# 04-USB-TFT.net
KiCad netlist of a schematic drawn in Altium Designer
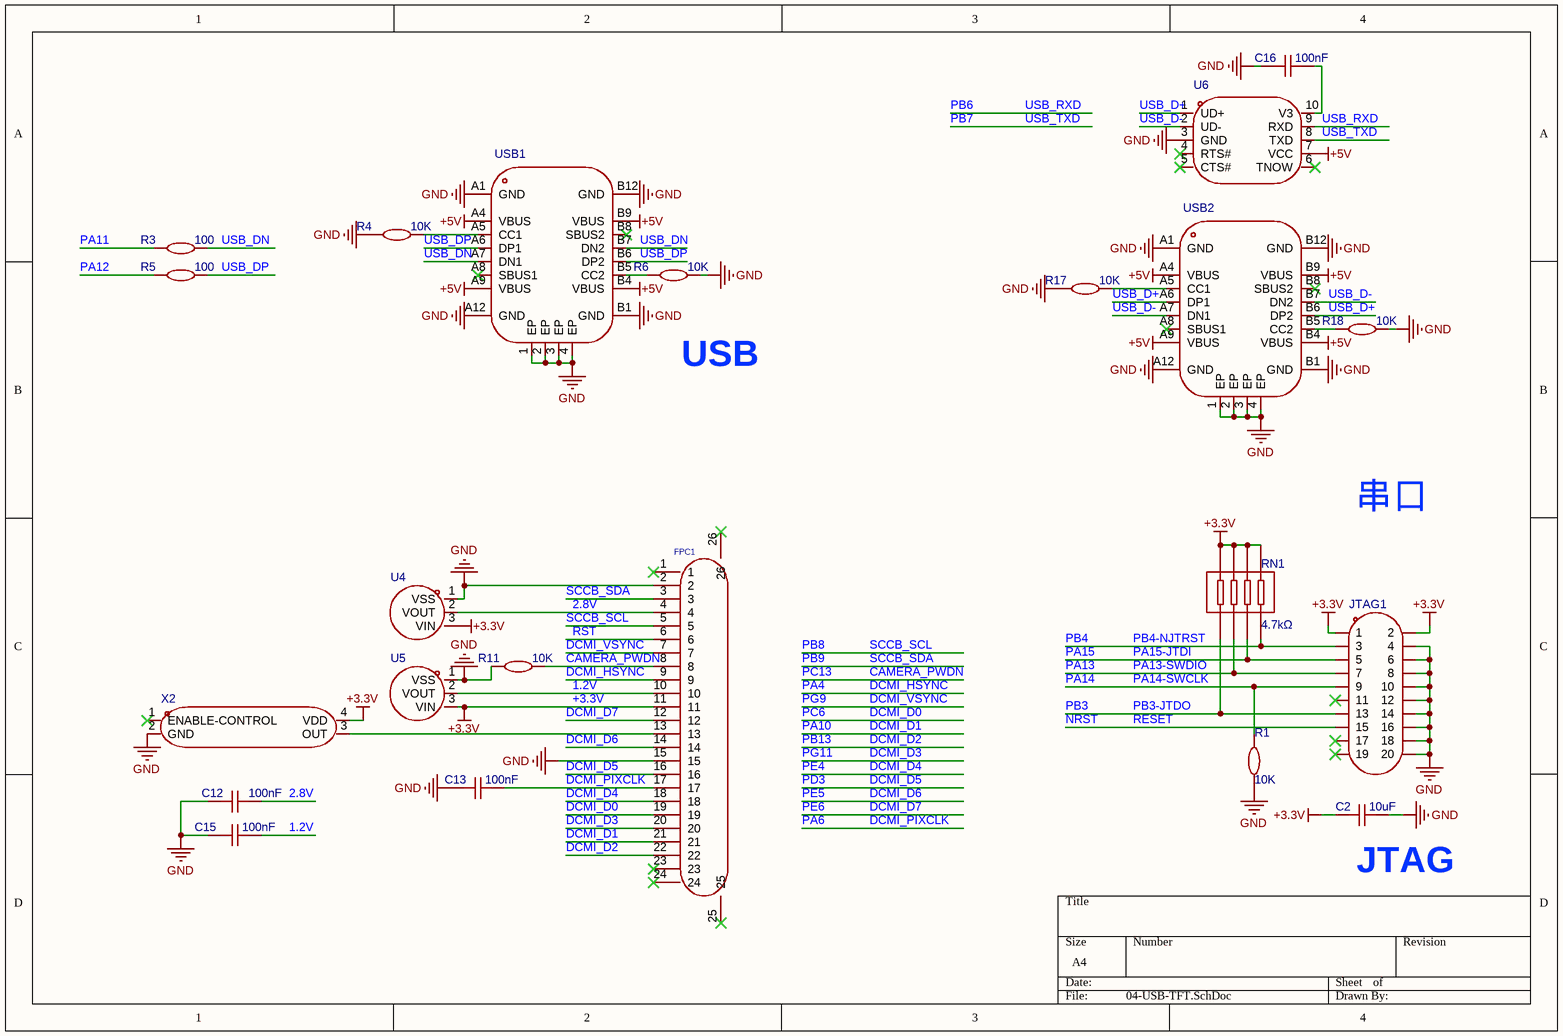
[diagram p0: 04-USB-TFT.SchDoc]

(export (version "E")
  (design (tool "Eeschema 10.0.6"))
  (components
    (comp (ref "C2")
      (value "10uF")
      (footprint "C0603")
      (fields (field (name "Comment") "CAP_0603"))
      (libsource (lib "altium-import") (part "root_0_CAP_0603_"))
    )
    (comp (ref "C12")
      (value "100nF")
      (footprint "C0603")
      (fields (field (name "Comment") "CAP_0603"))
      (libsource (lib "altium-import") (part "root_0_CAP_0603_"))
    )
    (comp (ref "C13")
      (value "100nF")
      (footprint "C0603")
      (fields (field (name "Comment") "CAP_0603"))
      (libsource (lib "altium-import") (part "root_0_CAP_0603_"))
    )
    (comp (ref "C15")
      (value "100nF")
      (footprint "C0603")
      (fields (field (name "Comment") "CAP_0603"))
      (libsource (lib "altium-import") (part "root_0_CAP_0603_"))
    )
    (comp (ref "C16")
      (value "100nF")
      (footprint "C0603")
      (fields (field (name "Comment") "CAP_0603"))
      (libsource (lib "altium-import") (part "root_2_CAP_0603_"))
    )
    (comp (ref "FPC1")
      (value "AFC01-S24FCA-00")
      (footprint "FPC-SMD_P0.50-24P_FGS-XJ-H2.0")
      (description "间距:0.5mm;触点数量:24P;锁定特性:翻盖式;安装类型:卧贴;触点类型:下接;")
      (fields (field (name "MANUFACTURER") "JS(钜硕电子)"))
      (libsource (lib "altium-import") (part "root_0_AFC01-S24FCA-00_"))
    )
    (comp (ref "JTAG1")
      (value "IDC-20")
      (footprint "IDC-TH_20P-P2.54-V-R2-C10-S2.54")
      (libsource (lib "altium-import") (part "root_0_IDC-20_"))
    )
    (comp (ref "R1")
      (value "10K")
      (footprint "R0603")
      (fields (field (name "Comment") "Res_0603"))
      (libsource (lib "altium-import") (part "root_1_Res_0603_"))
    )
    (comp (ref "R3")
      (value "100")
      (footprint "R0603")
      (fields (field (name "Comment") "Res_0603"))
      (libsource (lib "altium-import") (part "root_0_Res_0603_"))
    )
    (comp (ref "R4")
      (value "10K")
      (footprint "R0603")
      (fields (field (name "Comment") "Res_0603"))
      (libsource (lib "altium-import") (part "root_0_Res_0603_"))
    )
    (comp (ref "R5")
      (value "100")
      (footprint "R0603")
      (fields (field (name "Comment") "Res_0603"))
      (libsource (lib "altium-import") (part "root_0_Res_0603_"))
    )
    (comp (ref "R6")
      (value "10K")
      (footprint "R0603")
      (fields (field (name "Comment") "Res_0603"))
      (libsource (lib "altium-import") (part "root_0_Res_0603_"))
    )
    (comp (ref "R11")
      (value "10K")
      (footprint "R0603")
      (fields (field (name "Comment") "Res_0603"))
      (libsource (lib "altium-import") (part "root_0_Res_0603_"))
    )
    (comp (ref "R17")
      (value "10K")
      (footprint "R0603")
      (fields (field (name "Comment") "Res_0603"))
      (libsource (lib "altium-import") (part "root_0_Res_0603_"))
    )
    (comp (ref "R18")
      (value "10K")
      (footprint "R0603")
      (fields (field (name "Comment") "Res_0603"))
      (libsource (lib "altium-import") (part "root_0_Res_0603_"))
    )
    (comp (ref "RN1")
      (value "4.7kΩ")
      (footprint "RES-ARRAY-SMD_0603-8P-L3.2-W1.6-BL")
      (description "阻值:4.7kΩ;精度:±5%;单个元件功率:62.5mW;电阻器数:4;温度系数:±200ppm/℃;")
      (fields
        (field (name "MANUFACTURER") "UNI-ROYAL(厚声)")
        (field (name "MANUFACTURER PART") "4D03WGJ0472T5E")
      )
      (libsource (lib "altium-import") (part "root_1_4D03WGJ0472T5E_"))
    )
    (comp (ref "U4")
      (value "XC6206-2.8V")
      (footprint "SOT-23-3_L2.9-W1.6-P1.90-LS2.8-BR")
      (description "输出类型:固定;输出极性:正;最大输入电压:6V;输出电压:2.8V;输出电流:250mA;")
      (fields (field (name "MANUFACTURER") "YONGYUTAI(永裕泰)"))
      (libsource (lib "altium-import") (part "root_0_mirrored_XC6206-2.8V_"))
    )
    (comp (ref "U5")
      (value "XC6206P122MR-G")
      (footprint "SOT-23-3_L2.9-W1.6-P1.90-LS2.8-BR")
      (description "输出类型:固定;输出极性:正;最大输入电压:7V;输出电压:1.2V~1.2V;输出电流:60mA;电源纹波抑制比(PSRR):-;")
      (fields (field (name "MANUFACTURER") "TOREX(特瑞仕)"))
      (libsource (lib "altium-import") (part "root_0_mirrored_XC6206P122MR-G_"))
    )
    (comp (ref "U6")
      (value "CH340E")
      (footprint "MSOP-10_L3.0-W3.0-P0.50-LS5.0-BL")
      (description "应用功能:收发器;接口协议:USB 2.0;数据速率:2Mbps;")
      (fields (field (name "MANUFACTURER") "WCH(南京沁恒)"))
      (libsource (lib "altium-import") (part "root_0_CH340E_"))
    )
    (comp (ref "USB1")
      (value "USB_TYPE-C-16P")
      (footprint "USB_TYPE-C-16P")
      (libsource (lib "altium-import") (part "root_0_USB_TYPE-C-16P_"))
    )
    (comp (ref "USB2")
      (value "USB_TYPE-C-16P")
      (footprint "USB_TYPE-C-16P")
      (libsource (lib "altium-import") (part "root_0_USB_TYPE-C-16P_"))
    )
    (comp (ref "X2")
      (value "12M 有源晶振")
      (footprint "OSC-SMD_4P-L3.2-W2.5-BL")
      (libsource (lib "altium-import") (part "root_0_12M 有源晶振_"))
    )
  )
  (nets
    (net (code "1") (name "+3.3V") (class "Default")
      (node (ref "C2") (pin "1") (pinfunction "1_1") (pintype "passive"))
      (node (ref "FPC1") (pin "11") (pinfunction "11_11") (pintype "passive"))
      (node (ref "JTAG1") (pin "1") (pinfunction "1_1") (pintype "passive"))
      (node (ref "JTAG1") (pin "2") (pinfunction "2_2") (pintype "passive"))
      (node (ref "RN1") (pin "5") (pinfunction "5_5") (pintype "passive"))
      (node (ref "RN1") (pin "6") (pinfunction "6_6") (pintype "passive"))
      (node (ref "RN1") (pin "7") (pinfunction "7_7") (pintype "passive"))
      (node (ref "RN1") (pin "8") (pinfunction "8_8") (pintype "passive"))
      (node (ref "U4") (pin "3") (pinfunction "VIN_3") (pintype "passive"))
      (node (ref "U5") (pin "3") (pinfunction "VIN_3") (pintype "passive"))
      (node (ref "X2") (pin "4") (pinfunction "VDD_4") (pintype "passive"))
    )
    (net (code "2") (name "+5V") (class "Default")
      (node (ref "U6") (pin "7") (pinfunction "VCC_7") (pintype "passive"))
      (node (ref "USB1") (pin "A4") (pinfunction "VBUS_A4") (pintype "passive"))
      (node (ref "USB1") (pin "A9") (pinfunction "VBUS_A9") (pintype "passive"))
      (node (ref "USB1") (pin "B4") (pinfunction "VBUS_B4") (pintype "passive"))
      (node (ref "USB1") (pin "B9") (pinfunction "VBUS_B9") (pintype "passive"))
      (node (ref "USB2") (pin "A4") (pinfunction "VBUS_A4") (pintype "passive"))
      (node (ref "USB2") (pin "A9") (pinfunction "VBUS_A9") (pintype "passive"))
      (node (ref "USB2") (pin "B4") (pinfunction "VBUS_B4") (pintype "passive"))
      (node (ref "USB2") (pin "B9") (pinfunction "VBUS_B9") (pintype "passive"))
    )
    (net (code "3") (name "/1.2V") (class "Default")
      (node (ref "C15") (pin "2") (pinfunction "2_2") (pintype "passive"))
      (node (ref "FPC1") (pin "10") (pinfunction "10_10") (pintype "passive"))
      (node (ref "U5") (pin "2") (pinfunction "VOUT_2") (pintype "passive"))
    )
    (net (code "4") (name "/2.8V") (class "Default")
      (node (ref "C12") (pin "2") (pinfunction "2_2") (pintype "passive"))
      (node (ref "FPC1") (pin "4") (pinfunction "4_4") (pintype "passive"))
      (node (ref "U4") (pin "2") (pinfunction "VOUT_2") (pintype "passive"))
    )
    (net (code "5") (name "/CAMERA_PWDN") (class "Default")
      (node (ref "FPC1") (pin "8") (pinfunction "8_8") (pintype "passive"))
      (node (ref "R11") (pin "2") (pinfunction "2_2") (pintype "passive"))
    )
    (net (code "6") (name "/DCMI_D0") (class "Default")
      (node (ref "FPC1") (pin "19") (pinfunction "19_19") (pintype "passive"))
    )
    (net (code "7") (name "/DCMI_D1") (class "Default")
      (node (ref "FPC1") (pin "21") (pinfunction "21_21") (pintype "passive"))
    )
    (net (code "8") (name "/DCMI_D2") (class "Default")
      (node (ref "FPC1") (pin "22") (pinfunction "22_22") (pintype "passive"))
    )
    (net (code "9") (name "/DCMI_D3") (class "Default")
      (node (ref "FPC1") (pin "20") (pinfunction "20_20") (pintype "passive"))
    )
    (net (code "10") (name "/DCMI_D4") (class "Default")
      (node (ref "FPC1") (pin "18") (pinfunction "18_18") (pintype "passive"))
    )
    (net (code "11") (name "/DCMI_D5") (class "Default")
      (node (ref "FPC1") (pin "16") (pinfunction "16_16") (pintype "passive"))
    )
    (net (code "12") (name "/DCMI_D6") (class "Default")
      (node (ref "FPC1") (pin "14") (pinfunction "14_14") (pintype "passive"))
    )
    (net (code "13") (name "/DCMI_D7") (class "Default")
      (node (ref "FPC1") (pin "12") (pinfunction "12_12") (pintype "passive"))
    )
    (net (code "14") (name "/DCMI_HSYNC") (class "Default")
      (node (ref "FPC1") (pin "9") (pinfunction "9_9") (pintype "passive"))
    )
    (net (code "15") (name "/DCMI_PIXCLK") (class "Default")
      (node (ref "C13") (pin "2") (pinfunction "2_2") (pintype "passive"))
      (node (ref "FPC1") (pin "17") (pinfunction "17_17") (pintype "passive"))
    )
    (net (code "16") (name "/DCMI_VSYNC") (class "Default")
      (node (ref "FPC1") (pin "7") (pinfunction "7_7") (pintype "passive"))
    )
    (net (code "17") (name "/NRST") (class "Default")
      (node (ref "JTAG1") (pin "15") (pinfunction "15_15") (pintype "passive"))
    )
    (net (code "18") (name "/PA11") (class "Default")
      (node (ref "R3") (pin "1") (pinfunction "1_1") (pintype "passive"))
    )
    (net (code "19") (name "/PA12") (class "Default")
      (node (ref "R5") (pin "1") (pinfunction "1_1") (pintype "passive"))
    )
    (net (code "20") (name "/PA13") (class "Default")
      (node (ref "JTAG1") (pin "7") (pinfunction "7_7") (pintype "passive"))
      (node (ref "RN1") (pin "2") (pinfunction "2_2") (pintype "passive"))
    )
    (net (code "21") (name "/PA14") (class "Default")
      (node (ref "JTAG1") (pin "9") (pinfunction "9_9") (pintype "passive"))
      (node (ref "R1") (pin "2") (pinfunction "2_2") (pintype "passive"))
    )
    (net (code "22") (name "/PA15") (class "Default")
      (node (ref "JTAG1") (pin "5") (pinfunction "5_5") (pintype "passive"))
      (node (ref "RN1") (pin "3") (pinfunction "3_3") (pintype "passive"))
    )
    (net (code "23") (name "/PB3") (class "Default")
      (node (ref "JTAG1") (pin "13") (pinfunction "13_13") (pintype "passive"))
      (node (ref "RN1") (pin "1") (pinfunction "1_1") (pintype "passive"))
    )
    (net (code "24") (name "/PB4") (class "Default")
      (node (ref "JTAG1") (pin "3") (pinfunction "3_3") (pintype "passive"))
      (node (ref "RN1") (pin "4") (pinfunction "4_4") (pintype "passive"))
    )
    (net (code "25") (name "/PB6") (class "Default")
      (node (ref "U6") (pin "9") (pinfunction "RXD_9") (pintype "passive"))
    )
    (net (code "26") (name "/PB7") (class "Default")
      (node (ref "U6") (pin "8") (pinfunction "TXD_8") (pintype "passive"))
    )
    (net (code "27") (name "/PB8") (class "Default")
      (node (ref "FPC1") (pin "5") (pinfunction "5_5") (pintype "passive"))
    )
    (net (code "28") (name "/PB9") (class "Default")
      (node (ref "FPC1") (pin "3") (pinfunction "3_3") (pintype "passive"))
    )
    (net (code "29") (name "/RST") (class "Default")
      (node (ref "FPC1") (pin "6") (pinfunction "6_6") (pintype "passive"))
    )
    (net (code "30") (name "/USB_D+") (class "Default")
      (node (ref "U6") (pin "1") (pinfunction "UD+_1") (pintype "passive"))
      (node (ref "USB2") (pin "A6") (pinfunction "DP1_A6") (pintype "passive"))
      (node (ref "USB2") (pin "B6") (pinfunction "DP2_B6") (pintype "passive"))
    )
    (net (code "31") (name "/USB_D-") (class "Default")
      (node (ref "U6") (pin "2") (pinfunction "UD-_2") (pintype "passive"))
      (node (ref "USB2") (pin "A7") (pinfunction "DN1_A7") (pintype "passive"))
      (node (ref "USB2") (pin "B7") (pinfunction "DN2_B7") (pintype "passive"))
    )
    (net (code "32") (name "/USB_DN") (class "Default")
      (node (ref "R3") (pin "2") (pinfunction "2_2") (pintype "passive"))
      (node (ref "USB1") (pin "A7") (pinfunction "DN1_A7") (pintype "passive"))
      (node (ref "USB1") (pin "B7") (pinfunction "DN2_B7") (pintype "passive"))
    )
    (net (code "33") (name "/USB_DP") (class "Default")
      (node (ref "R5") (pin "2") (pinfunction "2_2") (pintype "passive"))
      (node (ref "USB1") (pin "A6") (pinfunction "DP1_A6") (pintype "passive"))
      (node (ref "USB1") (pin "B6") (pinfunction "DP2_B6") (pintype "passive"))
    )
    (net (code "34") (name "GND") (class "Default")
      (node (ref "C12") (pin "1") (pinfunction "1_1") (pintype "passive"))
      (node (ref "C13") (pin "1") (pinfunction "1_1") (pintype "passive"))
      (node (ref "C15") (pin "1") (pinfunction "1_1") (pintype "passive"))
      (node (ref "C16") (pin "2") (pinfunction "2_2") (pintype "passive"))
      (node (ref "C2") (pin "2") (pinfunction "2_2") (pintype "passive"))
      (node (ref "FPC1") (pin "15") (pinfunction "15_15") (pintype "passive"))
      (node (ref "FPC1") (pin "2") (pinfunction "2_2") (pintype "passive"))
      (node (ref "JTAG1") (pin "10") (pinfunction "10_10") (pintype "passive"))
      (node (ref "JTAG1") (pin "12") (pinfunction "12_12") (pintype "passive"))
      (node (ref "JTAG1") (pin "14") (pinfunction "14_14") (pintype "passive"))
      (node (ref "JTAG1") (pin "16") (pinfunction "16_16") (pintype "passive"))
      (node (ref "JTAG1") (pin "18") (pinfunction "18_18") (pintype "passive"))
      (node (ref "JTAG1") (pin "20") (pinfunction "20_20") (pintype "passive"))
      (node (ref "JTAG1") (pin "4") (pinfunction "4_4") (pintype "passive"))
      (node (ref "JTAG1") (pin "6") (pinfunction "6_6") (pintype "passive"))
      (node (ref "JTAG1") (pin "8") (pinfunction "8_8") (pintype "passive"))
      (node (ref "R1") (pin "1") (pinfunction "1_1") (pintype "passive"))
      (node (ref "R11") (pin "1") (pinfunction "1_1") (pintype "passive"))
      (node (ref "R17") (pin "1") (pinfunction "1_1") (pintype "passive"))
      (node (ref "R18") (pin "2") (pinfunction "2_2") (pintype "passive"))
      (node (ref "R4") (pin "1") (pinfunction "1_1") (pintype "passive"))
      (node (ref "R6") (pin "2") (pinfunction "2_2") (pintype "passive"))
      (node (ref "U4") (pin "1") (pinfunction "VSS_1") (pintype "passive"))
      (node (ref "U5") (pin "1") (pinfunction "VSS_1") (pintype "passive"))
      (node (ref "U6") (pin "3") (pinfunction "GND_3") (pintype "passive"))
      (node (ref "USB1") (pin "1") (pinfunction "EP_1") (pintype "passive"))
      (node (ref "USB1") (pin "2") (pinfunction "EP_2") (pintype "passive"))
      (node (ref "USB1") (pin "3") (pinfunction "EP_3") (pintype "passive"))
      (node (ref "USB1") (pin "4") (pinfunction "EP_4") (pintype "passive"))
      (node (ref "USB1") (pin "A1") (pinfunction "GND_A1") (pintype "passive"))
      (node (ref "USB1") (pin "A12") (pinfunction "GND_A12") (pintype "passive"))
      (node (ref "USB1") (pin "B1") (pinfunction "GND_B1") (pintype "passive"))
      (node (ref "USB1") (pin "B12") (pinfunction "GND_B12") (pintype "passive"))
      (node (ref "USB2") (pin "1") (pinfunction "EP_1") (pintype "passive"))
      (node (ref "USB2") (pin "2") (pinfunction "EP_2") (pintype "passive"))
      (node (ref "USB2") (pin "3") (pinfunction "EP_3") (pintype "passive"))
      (node (ref "USB2") (pin "4") (pinfunction "EP_4") (pintype "passive"))
      (node (ref "USB2") (pin "A1") (pinfunction "GND_A1") (pintype "passive"))
      (node (ref "USB2") (pin "A12") (pinfunction "GND_A12") (pintype "passive"))
      (node (ref "USB2") (pin "B1") (pinfunction "GND_B1") (pintype "passive"))
      (node (ref "USB2") (pin "B12") (pinfunction "GND_B12") (pintype "passive"))
      (node (ref "X2") (pin "2") (pinfunction "GND_2") (pintype "passive"))
    )
    (net (code "35") (name "Net-(U6-V3)") (class "Default")
      (node (ref "C16") (pin "1") (pinfunction "1_1") (pintype "passive"))
      (node (ref "U6") (pin "10") (pinfunction "V3_10") (pintype "passive"))
    )
    (net (code "36") (name "Net-(USB1-CC1)") (class "Default")
      (node (ref "R4") (pin "2") (pinfunction "2_2") (pintype "passive"))
      (node (ref "USB1") (pin "A5") (pinfunction "CC1_A5") (pintype "passive"))
    )
    (net (code "37") (name "Net-(USB1-CC2)") (class "Default")
      (node (ref "R6") (pin "1") (pinfunction "1_1") (pintype "passive"))
      (node (ref "USB1") (pin "B5") (pinfunction "CC2_B5") (pintype "passive"))
    )
    (net (code "38") (name "Net-(USB2-CC1)") (class "Default")
      (node (ref "R17") (pin "2") (pinfunction "2_2") (pintype "passive"))
      (node (ref "USB2") (pin "A5") (pinfunction "CC1_A5") (pintype "passive"))
    )
    (net (code "39") (name "Net-(USB2-CC2)") (class "Default")
      (node (ref "R18") (pin "1") (pinfunction "1_1") (pintype "passive"))
      (node (ref "USB2") (pin "B5") (pinfunction "CC2_B5") (pintype "passive"))
    )
    (net (code "40") (name "Net-(X2-OUT)") (class "Default")
      (node (ref "FPC1") (pin "13") (pinfunction "13_13") (pintype "passive"))
      (node (ref "X2") (pin "3") (pinfunction "OUT_3") (pintype "passive"))
    )
    (net (code "41") (name "unconnected-(FPC1-Pad1)") (class "Default")
      (node (ref "FPC1") (pin "1") (pinfunction "1_1") (pintype "passive+no_connect"))
    )
    (net (code "42") (name "unconnected-(FPC1-Pad23)") (class "Default")
      (node (ref "FPC1") (pin "23") (pinfunction "23_23") (pintype "passive+no_connect"))
    )
    (net (code "43") (name "unconnected-(FPC1-Pad24)") (class "Default")
      (node (ref "FPC1") (pin "24") (pinfunction "24_24") (pintype "passive+no_connect"))
    )
    (net (code "44") (name "unconnected-(FPC1-Pad25)") (class "Default")
      (node (ref "FPC1") (pin "25") (pinfunction "25_25") (pintype "passive+no_connect"))
    )
    (net (code "45") (name "unconnected-(FPC1-Pad26)") (class "Default")
      (node (ref "FPC1") (pin "26") (pinfunction "26_26") (pintype "passive+no_connect"))
    )
    (net (code "46") (name "unconnected-(JTAG1-Pad11)") (class "Default")
      (node (ref "JTAG1") (pin "11") (pinfunction "11_11") (pintype "passive+no_connect"))
    )
    (net (code "47") (name "unconnected-(JTAG1-Pad17)") (class "Default")
      (node (ref "JTAG1") (pin "17") (pinfunction "17_17") (pintype "passive+no_connect"))
    )
    (net (code "48") (name "unconnected-(JTAG1-Pad19)") (class "Default")
      (node (ref "JTAG1") (pin "19") (pinfunction "19_19") (pintype "passive+no_connect"))
    )
    (net (code "49") (name "unconnected-(U6-CTS#-Pad5)") (class "Default")
      (node (ref "U6") (pin "5") (pinfunction "CTS#_5") (pintype "passive+no_connect"))
    )
    (net (code "50") (name "unconnected-(U6-RTS#-Pad4)") (class "Default")
      (node (ref "U6") (pin "4") (pinfunction "RTS#_4") (pintype "passive+no_connect"))
    )
    (net (code "51") (name "unconnected-(U6-TNOW-Pad6)") (class "Default")
      (node (ref "U6") (pin "6") (pinfunction "TNOW_6") (pintype "passive+no_connect"))
    )
    (net (code "52") (name "unconnected-(USB1-SBUS1-PadA8)") (class "Default")
      (node (ref "USB1") (pin "A8") (pinfunction "SBUS1_A8") (pintype "passive+no_connect"))
    )
    (net (code "53") (name "unconnected-(USB1-SBUS2-PadB8)") (class "Default")
      (node (ref "USB1") (pin "B8") (pinfunction "SBUS2_B8") (pintype "passive+no_connect"))
    )
    (net (code "54") (name "unconnected-(USB2-SBUS1-PadA8)") (class "Default")
      (node (ref "USB2") (pin "A8") (pinfunction "SBUS1_A8") (pintype "passive+no_connect"))
    )
    (net (code "55") (name "unconnected-(USB2-SBUS2-PadB8)") (class "Default")
      (node (ref "USB2") (pin "B8") (pinfunction "SBUS2_B8") (pintype "passive+no_connect"))
    )
    (net (code "56") (name "unconnected-(X2-ENABLE-CONTROL-Pad1)") (class "Default")
      (node (ref "X2") (pin "1") (pinfunction "ENABLE-CONTROL_1") (pintype "passive+no_connect"))
    )
  )
)
